# 5_Changing_the_gain.net
KiCad netlist of a schematic drawn in Altium Designer
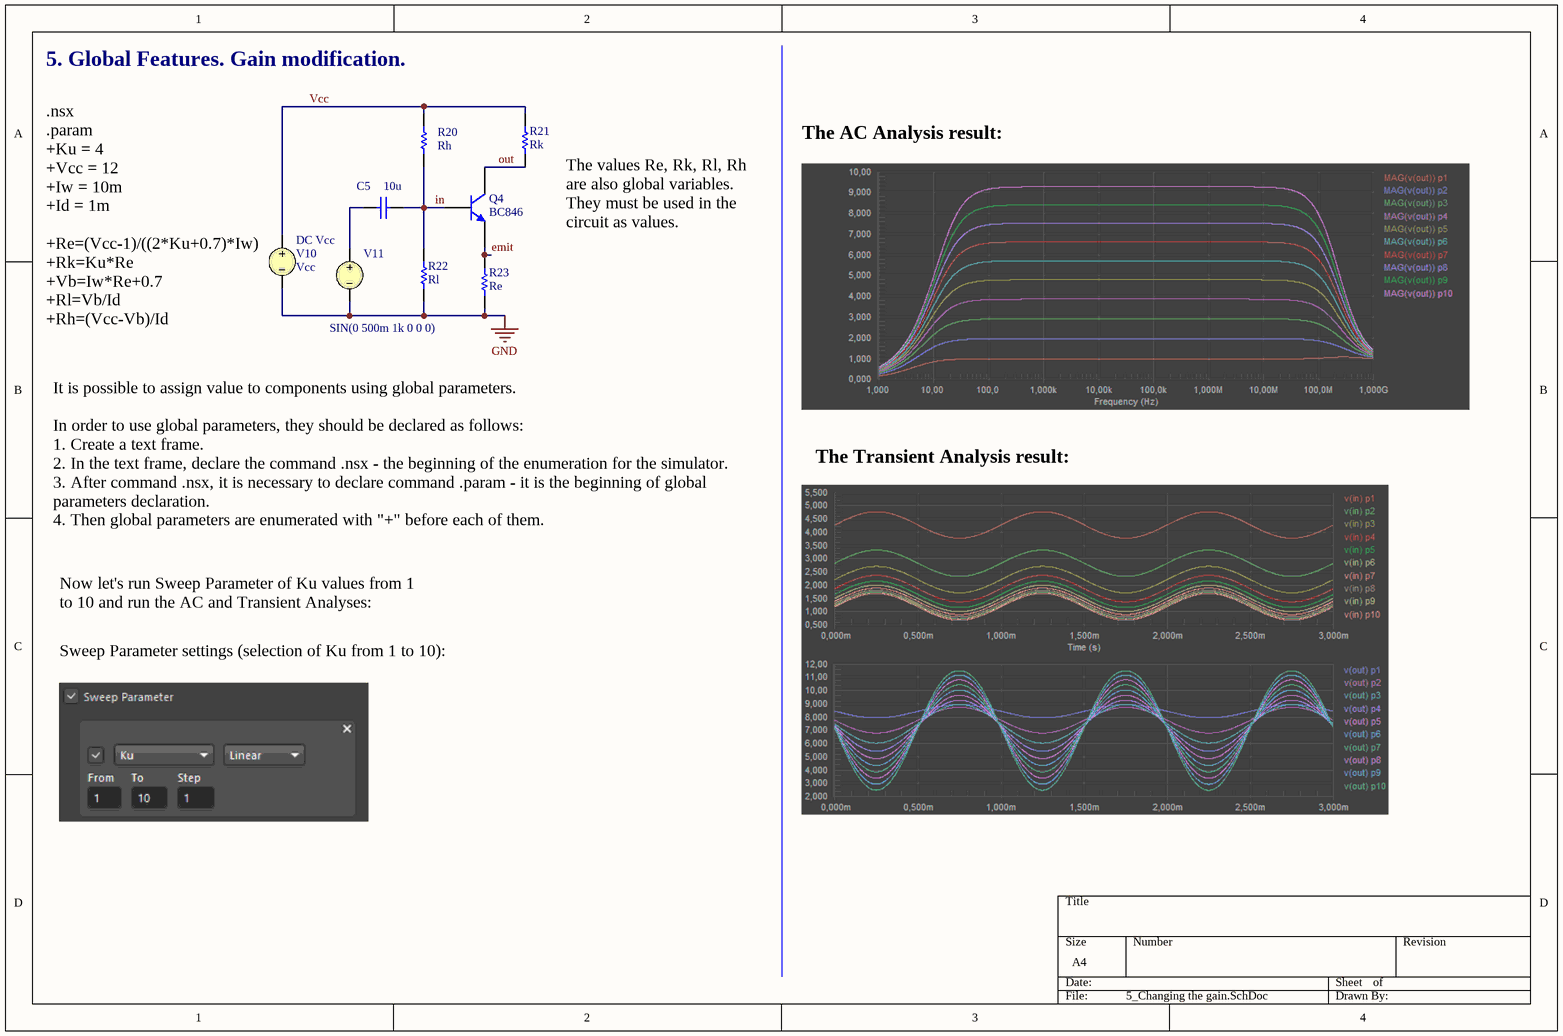
[diagram p0: 5_Changing the gain.SchDoc]

(export (version "E")
  (design (tool "Eeschema 10.0.6"))
  (components
    (comp (ref "C5")
      (value "10u")
      (description "Capacitor")
      (libsource (lib "Simulation Generic Components") (part "Capacitor"))
    )
    (comp (ref "Q4")
      (value "BC846")
      (footprint "TO-92A")
      (description "NPN General Purpose Amplifier")
      (fields (field (name "PUBLISHER") "Altium Limited"))
      (libsource (lib "Miscellaneous Devices") (part "2N3904"))
    )
    (comp (ref "R20")
      (value "Rh")
      (description "Resistor")
      (libsource (lib "Simulation Generic Components") (part "Resistor"))
    )
    (comp (ref "R21")
      (value "Rk")
      (description "Resistor")
      (libsource (lib "Simulation Generic Components") (part "Resistor"))
    )
    (comp (ref "R22")
      (value "Rl")
      (description "Resistor")
      (libsource (lib "Simulation Generic Components") (part "Resistor"))
    )
    (comp (ref "R23")
      (value "Re")
      (description "Resistor")
      (libsource (lib "Simulation Generic Components") (part "Resistor"))
    )
    (comp (ref "V10")
      (value "DC Vcc")
      (description "Voltage Source")
      (fields (field (name "ALTIUM_VALUE") "Vcc") (field (name "PUBLISHER") "Altium Limited"))
      (libsource (lib "Simulation Generic Components") (part "VSRC"))
    )
    (comp (ref "V11")
      (value "SIN(0 500m 1k 0 0 0)")
      (description "Voltage Source")
      (fields (field (name "PUBLISHER") "Altium Limited"))
      (libsource (lib "Simulation Generic Components") (part "VSRC"))
    )
  )
  (nets
    (net (code "1") (name "/Vcc") (class "Default")
      (node (ref "R20") (pin "2") (pinfunction "2_2") (pintype "passive"))
      (node (ref "R21") (pin "2") (pinfunction "2_2") (pintype "passive"))
      (node (ref "V10") (pin "1") (pinfunction "1_1") (pintype "passive"))
    )
    (net (code "2") (name "/emit") (class "Default")
      (node (ref "Q4") (pin "1") (pinfunction "E_1") (pintype "passive"))
      (node (ref "R23") (pin "2") (pinfunction "2_2") (pintype "passive"))
    )
    (net (code "3") (name "/in") (class "Default")
      (node (ref "C5") (pin "2") (pinfunction "2_2") (pintype "passive"))
      (node (ref "Q4") (pin "2") (pinfunction "B_2") (pintype "passive"))
      (node (ref "R20") (pin "1") (pinfunction "1_1") (pintype "passive"))
      (node (ref "R22") (pin "1") (pinfunction "1_1") (pintype "passive"))
    )
    (net (code "4") (name "/out") (class "Default")
      (node (ref "Q4") (pin "3") (pinfunction "C_3") (pintype "passive"))
      (node (ref "R21") (pin "1") (pinfunction "1_1") (pintype "passive"))
    )
    (net (code "5") (name "GND") (class "Default")
      (node (ref "R22") (pin "2") (pinfunction "2_2") (pintype "passive"))
      (node (ref "R23") (pin "1") (pinfunction "1_1") (pintype "passive"))
      (node (ref "V10") (pin "2") (pinfunction "2_2") (pintype "passive"))
      (node (ref "V11") (pin "2") (pinfunction "2_2") (pintype "passive"))
    )
    (net (code "6") (name "Net-(C5-Pad1)") (class "Default")
      (node (ref "C5") (pin "1") (pinfunction "1_1") (pintype "passive"))
      (node (ref "V11") (pin "1") (pinfunction "1_1") (pintype "passive"))
    )
  )
)
